# Motor_Ouptut.net
KiCad netlist of a schematic drawn in EAGLE
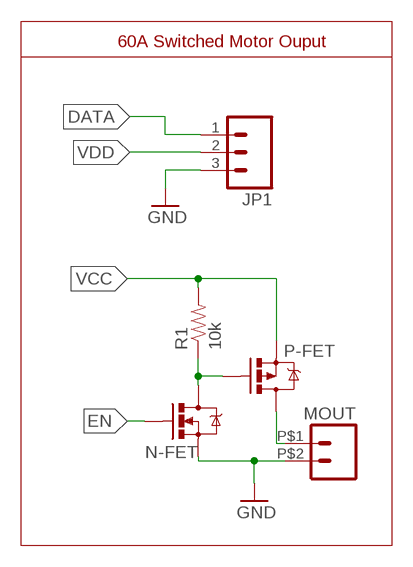
[diagram p0: schematic, sheet 1]

(export (version "E")
  (design (tool "Eeschema 10.0.6"))
  (components
    (comp (ref "JP1")
      (value "M03PTH")
      (footprint "eagle-import:1X03")
      (libsource (lib "eagle-import") (part "M03PTH"))
    )
    (comp (ref "MOUT")
      (value "MINI_FIT_JR_5569")
      (footprint "eagle-import:MINI_FIT_JR")
      (libsource (lib "eagle-import") (part "MINI_FIT_JR_5569"))
    )
    (comp (ref "N-FET")
      (value "MOSFET-NCHANNELBSS138")
      (footprint "eagle-import:SOT23")
      (libsource (lib "eagle-import") (part "MOSFET-NCHANNELBSS138"))
    )
    (comp (ref "P-FET")
      (value "MOSFET_P-CHANNEL")
      (footprint "eagle-import:POWERPAK_SO-8_SINGLE")
      (libsource (lib "eagle-import") (part "MOSFET_P-CHANNEL"))
    )
    (comp (ref "R1")
      (value "10k")
      (footprint "eagle-import:0603-RES")
      (libsource (lib "eagle-import") (part "RESISTOR0603-RES"))
    )
  )
  (nets
    (net (code "1") (name "DATA") (class "Default")
      (node (ref "JP1") (pin "1") (pinfunction "1_1") (pintype "passive"))
    )
    (net (code "2") (name "EN") (class "Default")
      (node (ref "N-FET") (pin "1") (pinfunction "G_1") (pintype "passive"))
    )
    (net (code "3") (name "GND") (class "Default")
      (node (ref "JP1") (pin "3") (pinfunction "3_3") (pintype "passive"))
    )
    (net (code "4") (name "Net-(MOUT-1)") (class "Default")
      (node (ref "MOUT") (pin "P$2") (pinfunction "1_P$2") (pintype "passive"))
      (node (ref "N-FET") (pin "2") (pinfunction "S_2") (pintype "passive"))
    )
    (net (code "5") (name "Net-(MOUT-2)") (class "Default")
      (node (ref "MOUT") (pin "P$1") (pinfunction "2_P$1") (pintype "passive"))
      (node (ref "P-FET") (pin "P$5") (pinfunction "D_P$5") (pintype "passive"))
      (node (ref "P-FET") (pin "P$6") (pinfunction "D_P$6") (pintype "passive"))
      (node (ref "P-FET") (pin "P$7") (pinfunction "D_P$7") (pintype "passive"))
      (node (ref "P-FET") (pin "P$8") (pinfunction "D_P$8") (pintype "passive"))
    )
    (net (code "6") (name "Net-(N-FET-D)") (class "Default")
      (node (ref "N-FET") (pin "3") (pinfunction "D_3") (pintype "passive"))
      (node (ref "P-FET") (pin "P$4") (pinfunction "G_P$4") (pintype "passive"))
      (node (ref "R1") (pin "1") (pinfunction "1_1") (pintype "passive"))
    )
    (net (code "7") (name "VCC") (class "Default")
      (node (ref "P-FET") (pin "P$1") (pinfunction "S_P$1") (pintype "passive"))
      (node (ref "P-FET") (pin "P$2") (pinfunction "S_P$2") (pintype "passive"))
      (node (ref "P-FET") (pin "P$3") (pinfunction "S_P$3") (pintype "passive"))
      (node (ref "R1") (pin "2") (pinfunction "2_2") (pintype "passive"))
    )
    (net (code "8") (name "VDD") (class "Default")
      (node (ref "JP1") (pin "2") (pinfunction "2_2") (pintype "passive"))
    )
  )
)
